# MBO.net
KiCad netlist of a schematic drawn in EAGLE
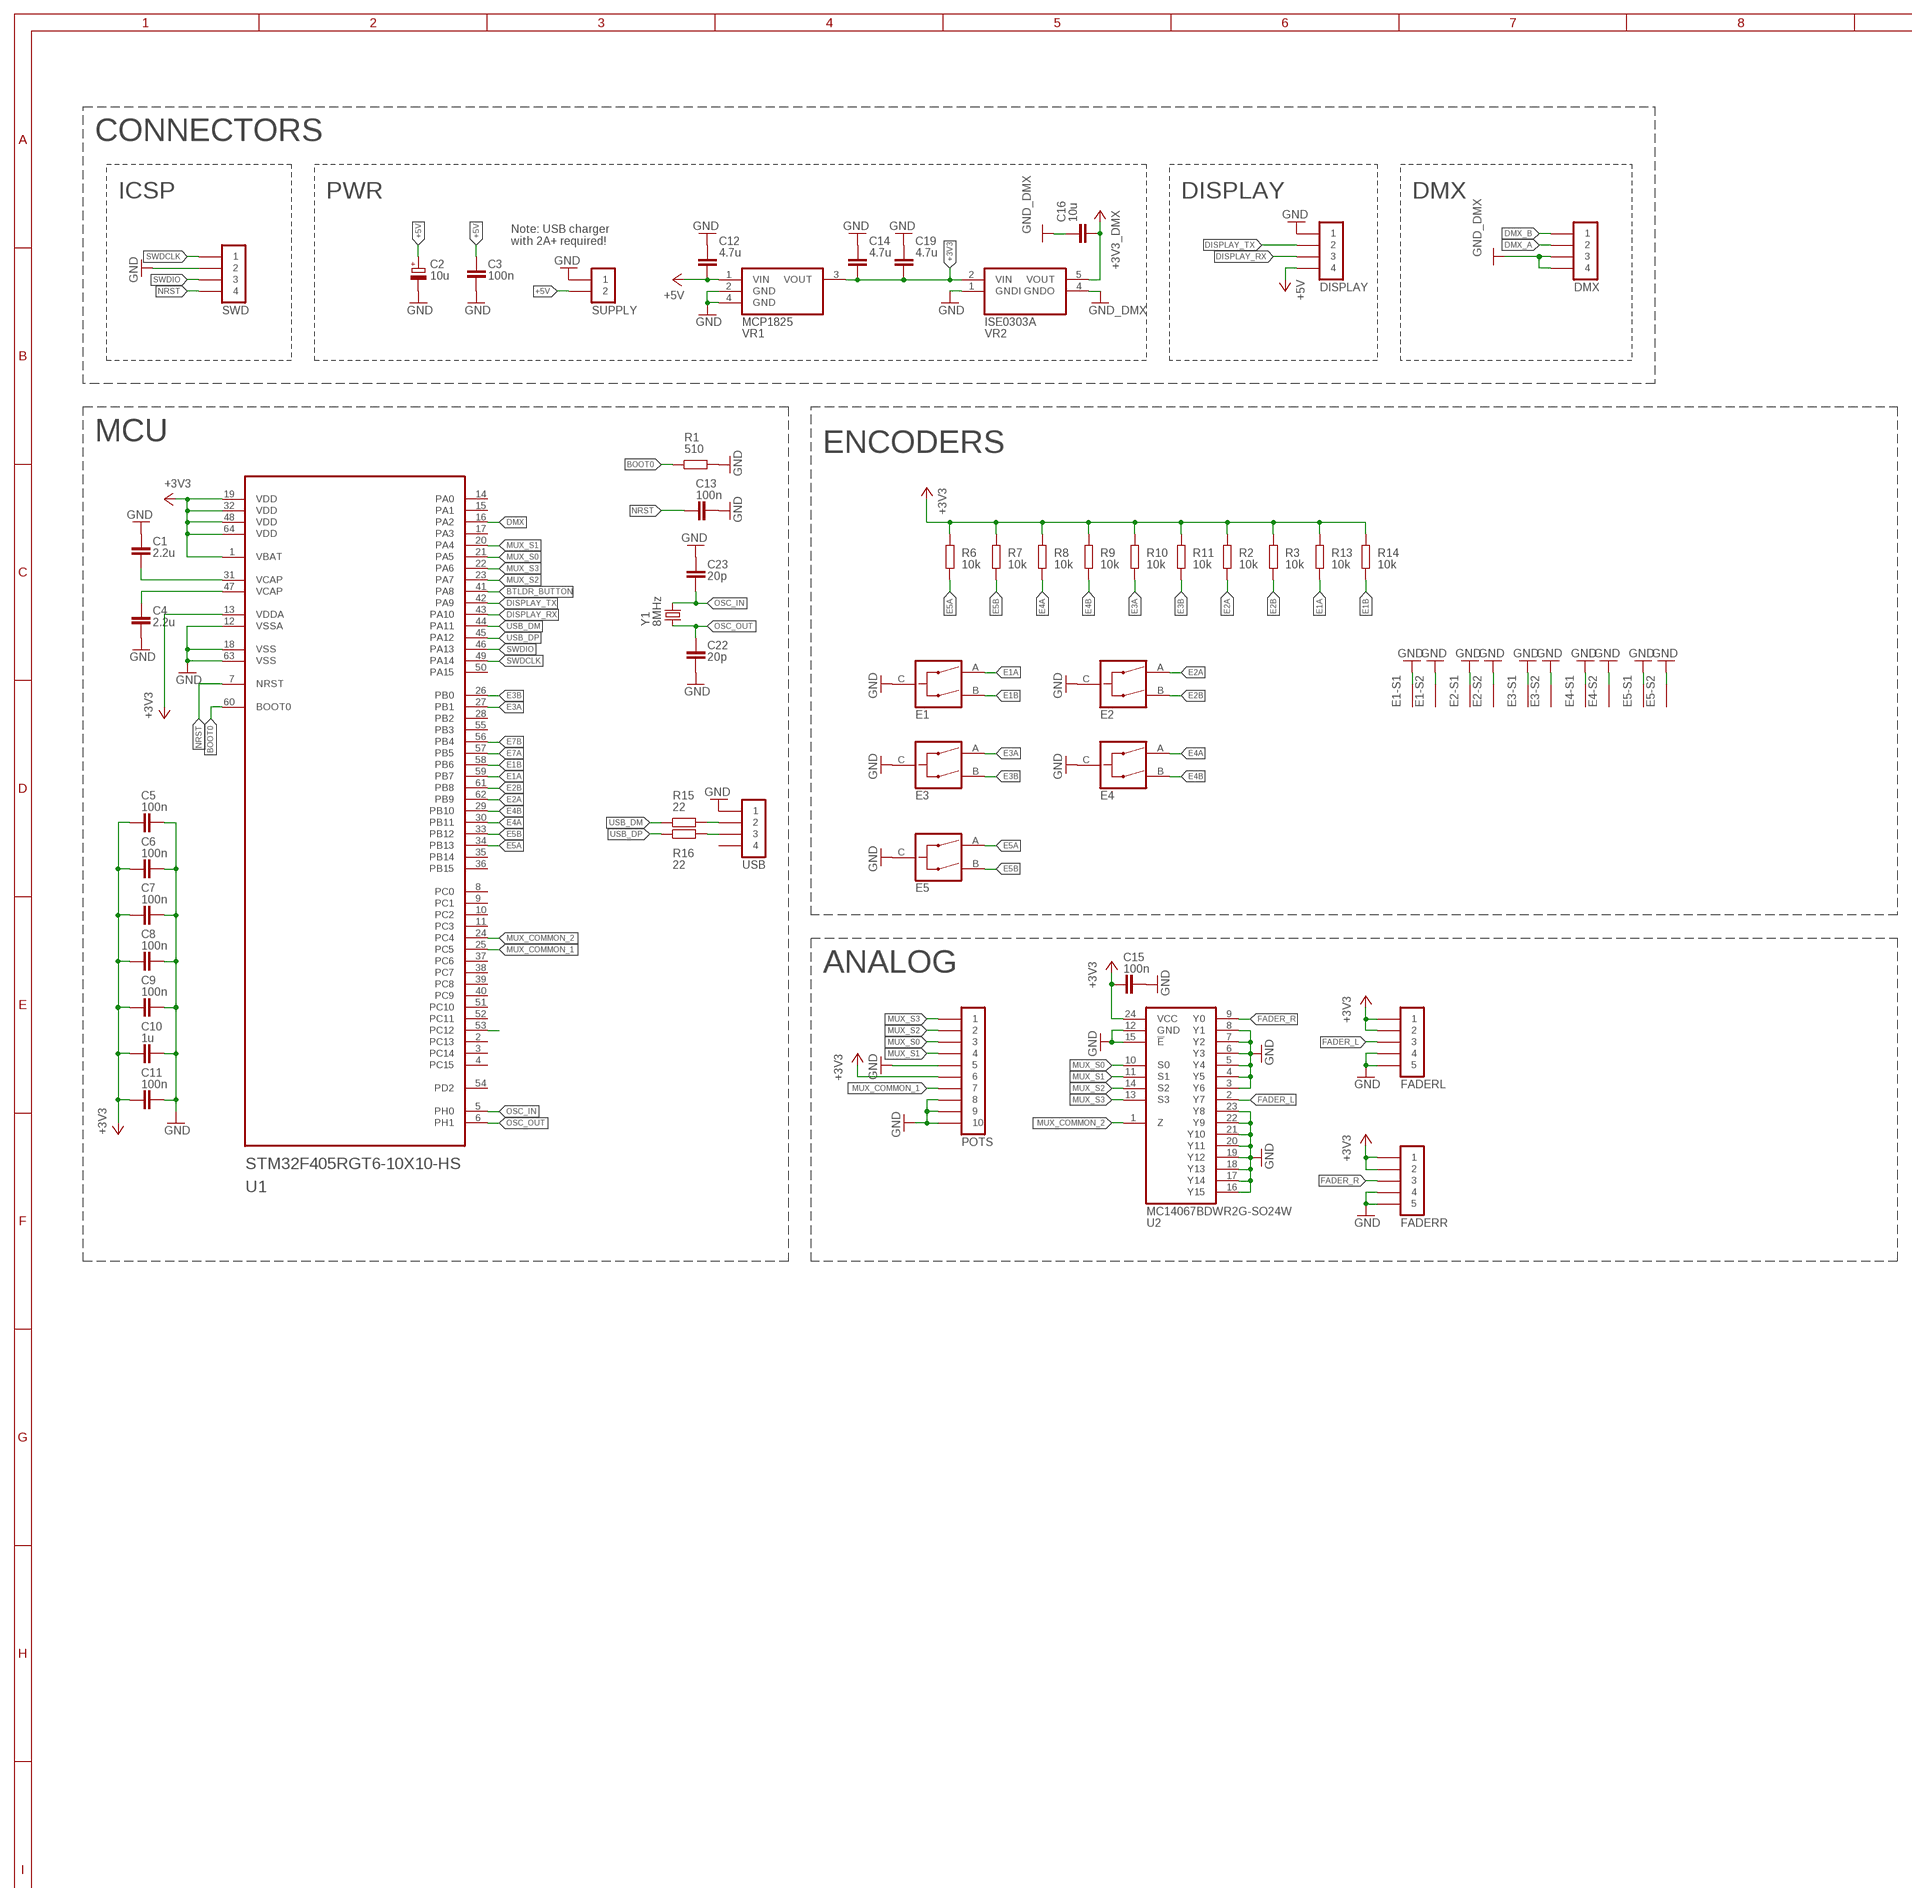
[diagram p0: schematic, sheet 1, part 1 of 2]
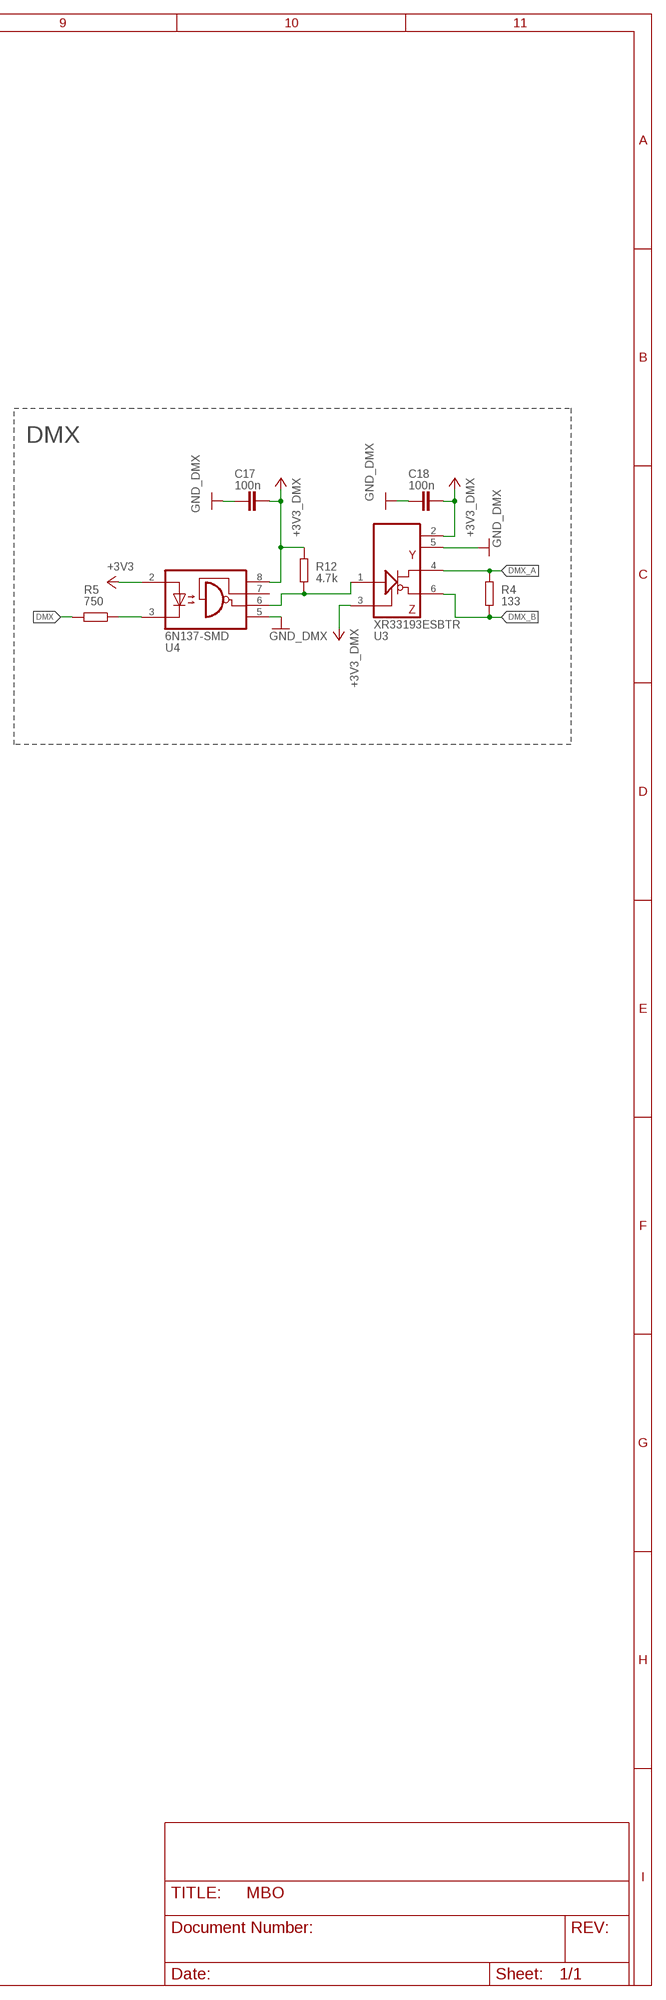
[diagram p1: schematic, sheet 1, part 2 of 2]

(export (version "E")
  (design (tool "Eeschema 10.0.6"))
  (components
    (comp (ref "C1")
      (value "2.2u")
      (footprint "eagle-import:C0805")
      (libsource (lib "eagle-import") (part "CAPACITOR-0805"))
    )
    (comp (ref "C2")
      (value "10u")
      (footprint "eagle-import:C-TH-E-0401")
      (libsource (lib "eagle-import") (part "ELECTROLYTIC_CAPACITOR-C-TH-E-0401"))
    )
    (comp (ref "C3")
      (value "100n")
      (footprint "eagle-import:C0805")
      (libsource (lib "eagle-import") (part "CAPACITOR-0805"))
    )
    (comp (ref "C4")
      (value "2.2u")
      (footprint "eagle-import:C0805")
      (libsource (lib "eagle-import") (part "CAPACITOR-0805"))
    )
    (comp (ref "C5")
      (value "100n")
      (footprint "eagle-import:C0805")
      (libsource (lib "eagle-import") (part "CAPACITOR-0805"))
    )
    (comp (ref "C6")
      (value "100n")
      (footprint "eagle-import:C0805")
      (libsource (lib "eagle-import") (part "CAPACITOR-0805"))
    )
    (comp (ref "C7")
      (value "100n")
      (footprint "eagle-import:C0805")
      (libsource (lib "eagle-import") (part "CAPACITOR-0805"))
    )
    (comp (ref "C8")
      (value "100n")
      (footprint "eagle-import:C0805")
      (libsource (lib "eagle-import") (part "CAPACITOR-0805"))
    )
    (comp (ref "C9")
      (value "100n")
      (footprint "eagle-import:C0805")
      (libsource (lib "eagle-import") (part "CAPACITOR-0805"))
    )
    (comp (ref "C10")
      (value "1u")
      (footprint "eagle-import:C0805")
      (libsource (lib "eagle-import") (part "CAPACITOR-0805"))
    )
    (comp (ref "C11")
      (value "100n")
      (footprint "eagle-import:C0805")
      (libsource (lib "eagle-import") (part "CAPACITOR-0805"))
    )
    (comp (ref "C12")
      (value "4.7u")
      (footprint "eagle-import:C0805")
      (libsource (lib "eagle-import") (part "CAPACITOR-0805"))
    )
    (comp (ref "C13")
      (value "100n")
      (footprint "eagle-import:C0805")
      (libsource (lib "eagle-import") (part "CAPACITOR-0805"))
    )
    (comp (ref "C14")
      (value "4.7u")
      (footprint "eagle-import:C0805")
      (libsource (lib "eagle-import") (part "CAPACITOR-0805"))
    )
    (comp (ref "C15")
      (value "100n")
      (footprint "eagle-import:C0805")
      (libsource (lib "eagle-import") (part "CAPACITOR-0805"))
    )
    (comp (ref "C16")
      (value "10u")
      (footprint "eagle-import:C0805")
      (libsource (lib "eagle-import") (part "CAPACITOR-0805"))
    )
    (comp (ref "C17")
      (value "100n")
      (footprint "eagle-import:C0805")
      (libsource (lib "eagle-import") (part "CAPACITOR-0805"))
    )
    (comp (ref "C18")
      (value "100n")
      (footprint "eagle-import:C0805")
      (libsource (lib "eagle-import") (part "CAPACITOR-0805"))
    )
    (comp (ref "C19")
      (value "4.7u")
      (footprint "eagle-import:C0805")
      (libsource (lib "eagle-import") (part "CAPACITOR-0805"))
    )
    (comp (ref "C22")
      (value "20p")
      (footprint "eagle-import:C0805")
      (libsource (lib "eagle-import") (part "CAPACITOR-0805"))
    )
    (comp (ref "C23")
      (value "20p")
      (footprint "eagle-import:C0805")
      (libsource (lib "eagle-import") (part "CAPACITOR-0805"))
    )
    (comp (ref "DISPLAY")
      (value "PINHD-1X04-JST-XH-H")
      (footprint "eagle-import:JST-XH-04P-H")
      (libsource (lib "eagle-import") (part "PINHD-1X04-JST-XH-H"))
    )
    (comp (ref "DMX")
      (value "PINHD-1X04-JST-XH-H")
      (footprint "eagle-import:JST-XH-04P-H")
      (libsource (lib "eagle-import") (part "PINHD-1X04-JST-XH-H"))
    )
    (comp (ref "E1")
      (value "ALPS-EC12E24404AX")
      (footprint "eagle-import:EC12E-1")
      (fields (field (name "MANUFACTURER") "ALPS") (field (name "MPN") "EC12E24404A8"))
      (libsource (lib "eagle-import") (part "ALPS-EC12E24404AX"))
    )
    (comp (ref "E2")
      (value "ALPS-EC12E24404AX")
      (footprint "eagle-import:EC12E-1")
      (fields (field (name "MANUFACTURER") "ALPS") (field (name "MPN") "EC12E24404A8"))
      (libsource (lib "eagle-import") (part "ALPS-EC12E24404AX"))
    )
    (comp (ref "E3")
      (value "ALPS-EC12E24404AX")
      (footprint "eagle-import:EC12E-1")
      (fields (field (name "MANUFACTURER") "ALPS") (field (name "MPN") "EC12E24404A8"))
      (libsource (lib "eagle-import") (part "ALPS-EC12E24404AX"))
    )
    (comp (ref "E4")
      (value "ALPS-EC12E24404AX")
      (footprint "eagle-import:EC12E-1")
      (fields (field (name "MANUFACTURER") "ALPS") (field (name "MPN") "EC12E24404A8"))
      (libsource (lib "eagle-import") (part "ALPS-EC12E24404AX"))
    )
    (comp (ref "E5")
      (value "ALPS-EC12E24404AX")
      (footprint "eagle-import:EC12E-1")
      (fields (field (name "MANUFACTURER") "ALPS") (field (name "MPN") "EC12E24404A8"))
      (libsource (lib "eagle-import") (part "ALPS-EC12E24404AX"))
    )
    (comp (ref "FADERL")
      (value "PINHD-1X05-FFC-1MM-Z")
      (footprint "eagle-import:MOLEX-52271-0579")
      (fields (field (name "MANUFACTURER") "Molex") (field (name "MPN") "52271-0579"))
      (libsource (lib "eagle-import") (part "PINHD-1X05-FFC-1MM-Z"))
    )
    (comp (ref "FADERR")
      (value "PINHD-1X05-FFC-1MM-Z")
      (footprint "eagle-import:MOLEX-52271-0579")
      (fields (field (name "MANUFACTURER") "Molex") (field (name "MPN") "52271-0579"))
      (libsource (lib "eagle-import") (part "PINHD-1X05-FFC-1MM-Z"))
    )
    (comp (ref "POTS")
      (value "PINHD-1X10-FFC-1MM-Z")
      (footprint "eagle-import:MOLEX-52271-1079")
      (fields (field (name "MANUFACTURER") "Molex") (field (name "MPN") "52271-1079"))
      (libsource (lib "eagle-import") (part "PINHD-1X10-FFC-1MM-Z"))
    )
    (comp (ref "R1")
      (value "510")
      (footprint "eagle-import:R0805")
      (libsource (lib "eagle-import") (part "RESISTOR-0805"))
    )
    (comp (ref "R2")
      (value "10k")
      (footprint "eagle-import:R0805")
      (libsource (lib "eagle-import") (part "RESISTOR-0805"))
    )
    (comp (ref "R3")
      (value "10k")
      (footprint "eagle-import:R0805")
      (libsource (lib "eagle-import") (part "RESISTOR-0805"))
    )
    (comp (ref "R4")
      (value "133")
      (footprint "eagle-import:R0805")
      (libsource (lib "eagle-import") (part "RESISTOR-0805"))
    )
    (comp (ref "R5")
      (value "750")
      (footprint "eagle-import:R0805")
      (libsource (lib "eagle-import") (part "RESISTOR-0805"))
    )
    (comp (ref "R6")
      (value "10k")
      (footprint "eagle-import:R0805")
      (libsource (lib "eagle-import") (part "RESISTOR-0805"))
    )
    (comp (ref "R7")
      (value "10k")
      (footprint "eagle-import:R0805")
      (libsource (lib "eagle-import") (part "RESISTOR-0805"))
    )
    (comp (ref "R8")
      (value "10k")
      (footprint "eagle-import:R0805")
      (libsource (lib "eagle-import") (part "RESISTOR-0805"))
    )
    (comp (ref "R9")
      (value "10k")
      (footprint "eagle-import:R0805")
      (libsource (lib "eagle-import") (part "RESISTOR-0805"))
    )
    (comp (ref "R10")
      (value "10k")
      (footprint "eagle-import:R0805")
      (libsource (lib "eagle-import") (part "RESISTOR-0805"))
    )
    (comp (ref "R11")
      (value "10k")
      (footprint "eagle-import:R0805")
      (libsource (lib "eagle-import") (part "RESISTOR-0805"))
    )
    (comp (ref "R12")
      (value "4.7k")
      (footprint "eagle-import:R0805")
      (libsource (lib "eagle-import") (part "RESISTOR-0805"))
    )
    (comp (ref "R13")
      (value "10k")
      (footprint "eagle-import:R0805")
      (libsource (lib "eagle-import") (part "RESISTOR-0805"))
    )
    (comp (ref "R14")
      (value "10k")
      (footprint "eagle-import:R0805")
      (libsource (lib "eagle-import") (part "RESISTOR-0805"))
    )
    (comp (ref "R15")
      (value "22")
      (footprint "eagle-import:R0805")
      (libsource (lib "eagle-import") (part "RESISTOR-0805"))
    )
    (comp (ref "R16")
      (value "22")
      (footprint "eagle-import:R0805")
      (libsource (lib "eagle-import") (part "RESISTOR-0805"))
    )
    (comp (ref "SUPPLY")
      (value "PINHD-1X02-JST-XH-H")
      (footprint "eagle-import:JST-XH-02P-H")
      (libsource (lib "eagle-import") (part "PINHD-1X02-JST-XH-H"))
    )
    (comp (ref "SWD")
      (value "PINHD-1X04-TH-2.54MM")
      (footprint "eagle-import:1X04-2.54")
      (libsource (lib "eagle-import") (part "PINHD-1X04-TH-2.54MM"))
    )
    (comp (ref "U1")
      (value "STM32F405RGT6-10X10-HS")
      (footprint "eagle-import:TQFP-64-10X10-HS")
      (fields (field (name "MANUFACTURER") "ST Microelectronics") (field (name "MPN") "STM32F405RGT6"))
      (libsource (lib "eagle-import") (part "STM32F405RGT6-10X10-HS"))
    )
    (comp (ref "U2")
      (value "MC14067BDWR2G-SO24W")
      (footprint "eagle-import:SO24-W")
      (fields (field (name "MANUFACTURER") "ON Semiconductor") (field (name "MPN") "MC14067BDWR2G"))
      (libsource (lib "eagle-import") (part "MC14067BDWR2G-SO24W"))
    )
    (comp (ref "U3")
      (value "XR33193ESBTR")
      (footprint "eagle-import:TSOT23-6")
      (fields (field (name "MANUFACTURER") "MaxLinear"))
      (libsource (lib "eagle-import") (part "XR33193ESBTR"))
    )
    (comp (ref "U4")
      (value "6N137-SMD")
      (footprint "eagle-import:SMD-8")
      (fields (field (name "MANUFACTURER") "Lite-On") (field (name "MPN") "6N137S"))
      (libsource (lib "eagle-import") (part "6N137-SMD"))
    )
    (comp (ref "USB")
      (value "PINHD-1X04-JST-XH-H")
      (footprint "eagle-import:JST-XH-04P-H")
      (libsource (lib "eagle-import") (part "PINHD-1X04-JST-XH-H"))
    )
    (comp (ref "VR1")
      (value "MCP1825")
      (footprint "eagle-import:SOT223")
      (fields (field (name "MANUFACTURER") "Microchip") (field (name "MPN") "MCP1825S-3302E/DB"))
      (libsource (lib "eagle-import") (part "MCP1825"))
    )
    (comp (ref "VR2")
      (value "ISE0303A")
      (footprint "eagle-import:SMD-8-5")
      (libsource (lib "eagle-import") (part "ISE0303A"))
    )
    (comp (ref "Y1")
      (value "8MHz")
      (footprint "eagle-import:HC49US")
      (fields (field (name "MANUFACTURER") "TXC") (field (name "MPN") "9B-16.000MEEJ-B"))
      (libsource (lib "eagle-import") (part "CRYSTAL-HC49"))
    )
  )
  (nets
    (net (code "1") (name "+3V3") (class "Default")
      (node (ref "C10") (pin "1") (pinfunction "1_1") (pintype "passive"))
      (node (ref "C11") (pin "1") (pinfunction "1_1") (pintype "passive"))
      (node (ref "C14") (pin "1") (pinfunction "1_1") (pintype "passive"))
      (node (ref "C15") (pin "1") (pinfunction "1_1") (pintype "passive"))
      (node (ref "C19") (pin "1") (pinfunction "1_1") (pintype "passive"))
      (node (ref "C5") (pin "1") (pinfunction "1_1") (pintype "passive"))
      (node (ref "C6") (pin "1") (pinfunction "1_1") (pintype "passive"))
      (node (ref "C7") (pin "1") (pinfunction "1_1") (pintype "passive"))
      (node (ref "C8") (pin "1") (pinfunction "1_1") (pintype "passive"))
      (node (ref "C9") (pin "1") (pinfunction "1_1") (pintype "passive"))
      (node (ref "FADERL") (pin "1") (pinfunction "1_1") (pintype "passive"))
      (node (ref "FADERL") (pin "2") (pinfunction "2_2") (pintype "passive"))
      (node (ref "FADERR") (pin "1") (pinfunction "1_1") (pintype "passive"))
      (node (ref "FADERR") (pin "2") (pinfunction "2_2") (pintype "passive"))
      (node (ref "POTS") (pin "6") (pinfunction "6_6") (pintype "passive"))
      (node (ref "R10") (pin "2") (pinfunction "2_2") (pintype "passive"))
      (node (ref "R11") (pin "2") (pinfunction "2_2") (pintype "passive"))
      (node (ref "R13") (pin "2") (pinfunction "2_2") (pintype "passive"))
      (node (ref "R14") (pin "2") (pinfunction "2_2") (pintype "passive"))
      (node (ref "R2") (pin "2") (pinfunction "2_2") (pintype "passive"))
      (node (ref "R3") (pin "2") (pinfunction "2_2") (pintype "passive"))
      (node (ref "R6") (pin "2") (pinfunction "2_2") (pintype "passive"))
      (node (ref "R7") (pin "2") (pinfunction "2_2") (pintype "passive"))
      (node (ref "R8") (pin "2") (pinfunction "2_2") (pintype "passive"))
      (node (ref "R9") (pin "2") (pinfunction "2_2") (pintype "passive"))
      (node (ref "U1") (pin "1") (pinfunction "VBAT_1") (pintype "bidirectional"))
      (node (ref "U1") (pin "13") (pinfunction "VDDA_13") (pintype "bidirectional"))
      (node (ref "U1") (pin "19") (pinfunction "VDD_19") (pintype "bidirectional"))
      (node (ref "U1") (pin "32") (pinfunction "VDD_32") (pintype "bidirectional"))
      (node (ref "U1") (pin "48") (pinfunction "VDD_48") (pintype "bidirectional"))
      (node (ref "U1") (pin "64") (pinfunction "VDD_64") (pintype "bidirectional"))
      (node (ref "U2") (pin "24") (pinfunction "VCC_24") (pintype "passive"))
      (node (ref "U4") (pin "2") (pinfunction "A_2") (pintype "passive"))
      (node (ref "VR1") (pin "3") (pinfunction "VOUT_3") (pintype "passive"))
      (node (ref "VR2") (pin "2") (pinfunction "VIN_2") (pintype "passive"))
    )
    (net (code "2") (name "+3V3_DMX") (class "Default")
      (node (ref "C16") (pin "1") (pinfunction "1_1") (pintype "passive"))
      (node (ref "C17") (pin "2") (pinfunction "2_2") (pintype "passive"))
      (node (ref "C18") (pin "2") (pinfunction "2_2") (pintype "passive"))
      (node (ref "R12") (pin "2") (pinfunction "2_2") (pintype "passive"))
      (node (ref "U3") (pin "2") (pinfunction "VCC_2") (pintype "passive"))
      (node (ref "U3") (pin "3") (pinfunction "DE_3") (pintype "bidirectional"))
      (node (ref "U4") (pin "8") (pinfunction "VCC_8") (pintype "power_in"))
      (node (ref "VR2") (pin "5") (pinfunction "VOUT_5") (pintype "passive"))
    )
    (net (code "3") (name "+5V") (class "Default")
      (node (ref "C12") (pin "1") (pinfunction "1_1") (pintype "passive"))
      (node (ref "C2") (pin "+") (pinfunction "+_+") (pintype "passive"))
      (node (ref "C3") (pin "1") (pinfunction "1_1") (pintype "passive"))
      (node (ref "DISPLAY") (pin "4") (pinfunction "4_4") (pintype "passive"))
      (node (ref "SUPPLY") (pin "2") (pinfunction "2_2") (pintype "passive"))
      (node (ref "VR1") (pin "1") (pinfunction "VIN_1") (pintype "passive"))
    )
    (net (code "4") (name "BOOT0") (class "Default")
      (node (ref "R1") (pin "1") (pinfunction "1_1") (pintype "passive"))
      (node (ref "U1") (pin "60") (pinfunction "BOOT0_60") (pintype "bidirectional"))
    )
    (net (code "5") (name "BTLDR_BUTTON") (class "Default")
      (node (ref "U1") (pin "41") (pinfunction "PA8_41") (pintype "bidirectional"))
    )
    (net (code "6") (name "DISPLAY_RX") (class "Default")
      (node (ref "DISPLAY") (pin "3") (pinfunction "3_3") (pintype "passive"))
      (node (ref "U1") (pin "43") (pinfunction "PA10_43") (pintype "bidirectional"))
    )
    (net (code "7") (name "DISPLAY_TX") (class "Default")
      (node (ref "DISPLAY") (pin "2") (pinfunction "2_2") (pintype "passive"))
      (node (ref "U1") (pin "42") (pinfunction "PA9_42") (pintype "bidirectional"))
    )
    (net (code "8") (name "DMX") (class "Default")
      (node (ref "R5") (pin "2") (pinfunction "2_2") (pintype "passive"))
      (node (ref "U1") (pin "16") (pinfunction "PA2_16") (pintype "bidirectional"))
    )
    (net (code "9") (name "DMX_A") (class "Default")
      (node (ref "DMX") (pin "2") (pinfunction "2_2") (pintype "passive"))
      (node (ref "R4") (pin "2") (pinfunction "2_2") (pintype "passive"))
      (node (ref "U3") (pin "4") (pinfunction "B_4") (pintype "output"))
    )
    (net (code "10") (name "DMX_B") (class "Default")
      (node (ref "DMX") (pin "1") (pinfunction "1_1") (pintype "passive"))
      (node (ref "R4") (pin "1") (pinfunction "1_1") (pintype "passive"))
      (node (ref "U3") (pin "6") (pinfunction "A_6") (pintype "output"))
    )
    (net (code "11") (name "E1A") (class "Default")
      (node (ref "E1") (pin "A") (pinfunction "A_A") (pintype "output"))
      (node (ref "R13") (pin "1") (pinfunction "1_1") (pintype "passive"))
      (node (ref "U1") (pin "59") (pinfunction "PB7_59") (pintype "bidirectional"))
    )
    (net (code "12") (name "E1B") (class "Default")
      (node (ref "E1") (pin "B") (pinfunction "B_B") (pintype "output"))
      (node (ref "R14") (pin "1") (pinfunction "1_1") (pintype "passive"))
      (node (ref "U1") (pin "58") (pinfunction "PB6_58") (pintype "bidirectional"))
    )
    (net (code "13") (name "E2A") (class "Default")
      (node (ref "E2") (pin "A") (pinfunction "A_A") (pintype "output"))
      (node (ref "R2") (pin "1") (pinfunction "1_1") (pintype "passive"))
      (node (ref "U1") (pin "62") (pinfunction "PB9_62") (pintype "bidirectional"))
    )
    (net (code "14") (name "E2B") (class "Default")
      (node (ref "E2") (pin "B") (pinfunction "B_B") (pintype "output"))
      (node (ref "R3") (pin "1") (pinfunction "1_1") (pintype "passive"))
      (node (ref "U1") (pin "61") (pinfunction "PB8_61") (pintype "bidirectional"))
    )
    (net (code "15") (name "E3A") (class "Default")
      (node (ref "E3") (pin "A") (pinfunction "A_A") (pintype "output"))
      (node (ref "R10") (pin "1") (pinfunction "1_1") (pintype "passive"))
      (node (ref "U1") (pin "27") (pinfunction "PB1_27") (pintype "bidirectional"))
    )
    (net (code "16") (name "E3B") (class "Default")
      (node (ref "E3") (pin "B") (pinfunction "B_B") (pintype "output"))
      (node (ref "R11") (pin "1") (pinfunction "1_1") (pintype "passive"))
      (node (ref "U1") (pin "26") (pinfunction "PB0_26") (pintype "bidirectional"))
    )
    (net (code "17") (name "E4A") (class "Default")
      (node (ref "E4") (pin "A") (pinfunction "A_A") (pintype "output"))
      (node (ref "R8") (pin "1") (pinfunction "1_1") (pintype "passive"))
      (node (ref "U1") (pin "30") (pinfunction "PB11_30") (pintype "bidirectional"))
    )
    (net (code "18") (name "E4B") (class "Default")
      (node (ref "E4") (pin "B") (pinfunction "B_B") (pintype "output"))
      (node (ref "R9") (pin "1") (pinfunction "1_1") (pintype "passive"))
      (node (ref "U1") (pin "29") (pinfunction "PB10_29") (pintype "bidirectional"))
    )
    (net (code "19") (name "E5A") (class "Default")
      (node (ref "E5") (pin "A") (pinfunction "A_A") (pintype "output"))
      (node (ref "R6") (pin "1") (pinfunction "1_1") (pintype "passive"))
      (node (ref "U1") (pin "34") (pinfunction "PB13_34") (pintype "bidirectional"))
    )
    (net (code "20") (name "E5B") (class "Default")
      (node (ref "E5") (pin "B") (pinfunction "B_B") (pintype "output"))
      (node (ref "R7") (pin "1") (pinfunction "1_1") (pintype "passive"))
      (node (ref "U1") (pin "33") (pinfunction "PB12_33") (pintype "bidirectional"))
    )
    (net (code "21") (name "E7A") (class "Default")
      (node (ref "U1") (pin "57") (pinfunction "PB5_57") (pintype "bidirectional"))
    )
    (net (code "22") (name "E7B") (class "Default")
      (node (ref "U1") (pin "56") (pinfunction "PB4_56") (pintype "bidirectional"))
    )
    (net (code "23") (name "FADER_L") (class "Default")
      (node (ref "FADERL") (pin "3") (pinfunction "3_3") (pintype "passive"))
      (node (ref "U2") (pin "2") (pinfunction "Y7_2") (pintype "bidirectional"))
    )
    (net (code "24") (name "FADER_R") (class "Default")
      (node (ref "FADERR") (pin "3") (pinfunction "3_3") (pintype "passive"))
      (node (ref "U2") (pin "9") (pinfunction "Y0_9") (pintype "bidirectional"))
    )
    (net (code "25") (name "GND") (class "Default")
      (node (ref "C1") (pin "1") (pinfunction "1_1") (pintype "passive"))
      (node (ref "C10") (pin "2") (pinfunction "2_2") (pintype "passive"))
      (node (ref "C11") (pin "2") (pinfunction "2_2") (pintype "passive"))
      (node (ref "C12") (pin "2") (pinfunction "2_2") (pintype "passive"))
      (node (ref "C13") (pin "2") (pinfunction "2_2") (pintype "passive"))
      (node (ref "C14") (pin "2") (pinfunction "2_2") (pintype "passive"))
      (node (ref "C15") (pin "2") (pinfunction "2_2") (pintype "passive"))
      (node (ref "C19") (pin "2") (pinfunction "2_2") (pintype "passive"))
      (node (ref "C2") (pin "-") (pinfunction "-_-") (pintype "passive"))
      (node (ref "C22") (pin "2") (pinfunction "2_2") (pintype "passive"))
      (node (ref "C23") (pin "1") (pinfunction "1_1") (pintype "passive"))
      (node (ref "C3") (pin "2") (pinfunction "2_2") (pintype "passive"))
      (node (ref "C4") (pin "2") (pinfunction "2_2") (pintype "passive"))
      (node (ref "C5") (pin "2") (pinfunction "2_2") (pintype "passive"))
      (node (ref "C6") (pin "2") (pinfunction "2_2") (pintype "passive"))
      (node (ref "C7") (pin "2") (pinfunction "2_2") (pintype "passive"))
      (node (ref "C8") (pin "2") (pinfunction "2_2") (pintype "passive"))
      (node (ref "C9") (pin "2") (pinfunction "2_2") (pintype "passive"))
      (node (ref "DISPLAY") (pin "1") (pinfunction "1_1") (pintype "passive"))
      (node (ref "E1") (pin "C") (pinfunction "C_C") (pintype "input"))
      (node (ref "E1") (pin "S1") (pinfunction "S_S1") (pintype "passive"))
      (node (ref "E1") (pin "S2") (pinfunction "S_S2") (pintype "passive"))
      (node (ref "E2") (pin "C") (pinfunction "C_C") (pintype "input"))
      (node (ref "E2") (pin "S1") (pinfunction "S_S1") (pintype "passive"))
      (node (ref "E2") (pin "S2") (pinfunction "S_S2") (pintype "passive"))
      (node (ref "E3") (pin "C") (pinfunction "C_C") (pintype "input"))
      (node (ref "E3") (pin "S1") (pinfunction "S_S1") (pintype "passive"))
      (node (ref "E3") (pin "S2") (pinfunction "S_S2") (pintype "passive"))
      (node (ref "E4") (pin "C") (pinfunction "C_C") (pintype "input"))
      (node (ref "E4") (pin "S1") (pinfunction "S_S1") (pintype "passive"))
      (node (ref "E4") (pin "S2") (pinfunction "S_S2") (pintype "passive"))
      (node (ref "E5") (pin "C") (pinfunction "C_C") (pintype "input"))
      (node (ref "E5") (pin "S1") (pinfunction "S_S1") (pintype "passive"))
      (node (ref "E5") (pin "S2") (pinfunction "S_S2") (pintype "passive"))
      (node (ref "FADERL") (pin "4") (pinfunction "4_4") (pintype "passive"))
      (node (ref "FADERL") (pin "5") (pinfunction "5_5") (pintype "passive"))
      (node (ref "FADERR") (pin "4") (pinfunction "4_4") (pintype "passive"))
      (node (ref "FADERR") (pin "5") (pinfunction "5_5") (pintype "passive"))
      (node (ref "POTS") (pin "10") (pinfunction "10_10") (pintype "passive"))
      (node (ref "POTS") (pin "5") (pinfunction "5_5") (pintype "passive"))
      (node (ref "POTS") (pin "8") (pinfunction "8_8") (pintype "passive"))
      (node (ref "POTS") (pin "9") (pinfunction "9_9") (pintype "passive"))
      (node (ref "R1") (pin "2") (pinfunction "2_2") (pintype "passive"))
      (node (ref "SUPPLY") (pin "1") (pinfunction "1_1") (pintype "passive"))
      (node (ref "SWD") (pin "2") (pinfunction "2_2") (pintype "passive"))
      (node (ref "U1") (pin "12") (pinfunction "VSSA_12") (pintype "bidirectional"))
      (node (ref "U1") (pin "18") (pinfunction "VSS_18") (pintype "bidirectional"))
      (node (ref "U1") (pin "63") (pinfunction "VSS_63") (pintype "bidirectional"))
      (node (ref "U2") (pin "12") (pinfunction "GND_12") (pintype "passive"))
      (node (ref "U2") (pin "15") (pinfunction "~{E}_15") (pintype "input"))
      (node (ref "U2") (pin "16") (pinfunction "Y15_16") (pintype "bidirectional"))
      (node (ref "U2") (pin "17") (pinfunction "Y14_17") (pintype "bidirectional"))
      (node (ref "U2") (pin "18") (pinfunction "Y13_18") (pintype "bidirectional"))
      (node (ref "U2") (pin "19") (pinfunction "Y12_19") (pintype "bidirectional"))
      (node (ref "U2") (pin "20") (pinfunction "Y11_20") (pintype "bidirectional"))
      (node (ref "U2") (pin "21") (pinfunction "Y10_21") (pintype "bidirectional"))
      (node (ref "U2") (pin "22") (pinfunction "Y9_22") (pintype "bidirectional"))
      (node (ref "U2") (pin "23") (pinfunction "Y8_23") (pintype "bidirectional"))
      (node (ref "U2") (pin "3") (pinfunction "Y6_3") (pintype "bidirectional"))
      (node (ref "U2") (pin "4") (pinfunction "Y5_4") (pintype "bidirectional"))
      (node (ref "U2") (pin "5") (pinfunction "Y4_5") (pintype "bidirectional"))
      (node (ref "U2") (pin "6") (pinfunction "Y3_6") (pintype "bidirectional"))
      (node (ref "U2") (pin "7") (pinfunction "Y2_7") (pintype "bidirectional"))
      (node (ref "U2") (pin "8") (pinfunction "Y1_8") (pintype "bidirectional"))
      (node (ref "USB") (pin "1") (pinfunction "1_1") (pintype "passive"))
      (node (ref "VR1") (pin "2") (pinfunction "GND_2") (pintype "passive"))
      (node (ref "VR1") (pin "4") (pinfunction "GND_4") (pintype "passive"))
      (node (ref "VR2") (pin "1") (pinfunction "GNDI_1") (pintype "passive"))
    )
    (net (code "26") (name "GND_DMX") (class "Default")
      (node (ref "C16") (pin "2") (pinfunction "2_2") (pintype "passive"))
      (node (ref "C17") (pin "1") (pinfunction "1_1") (pintype "passive"))
      (node (ref "C18") (pin "1") (pinfunction "1_1") (pintype "passive"))
      (node (ref "DMX") (pin "3") (pinfunction "3_3") (pintype "passive"))
      (node (ref "DMX") (pin "4") (pinfunction "4_4") (pintype "passive"))
      (node (ref "U3") (pin "5") (pinfunction "GND_5") (pintype "passive"))
      (node (ref "U4") (pin "5") (pinfunction "GND_5") (pintype "power_in"))
      (node (ref "VR2") (pin "4") (pinfunction "GNDO_4") (pintype "passive"))
    )
    (net (code "27") (name "MUX_COMMON_1") (class "Default")
      (node (ref "POTS") (pin "7") (pinfunction "7_7") (pintype "passive"))
      (node (ref "U1") (pin "25") (pinfunction "PC5_25") (pintype "bidirectional"))
    )
    (net (code "28") (name "MUX_COMMON_2") (class "Default")
      (node (ref "U1") (pin "24") (pinfunction "PC4_24") (pintype "bidirectional"))
      (node (ref "U2") (pin "1") (pinfunction "Z_1") (pintype "bidirectional"))
    )
    (net (code "29") (name "MUX_S0") (class "Default")
      (node (ref "POTS") (pin "3") (pinfunction "3_3") (pintype "passive"))
      (node (ref "U1") (pin "21") (pinfunction "PA5_21") (pintype "bidirectional"))
      (node (ref "U2") (pin "10") (pinfunction "S0_10") (pintype "input"))
    )
    (net (code "30") (name "MUX_S1") (class "Default")
      (node (ref "POTS") (pin "4") (pinfunction "4_4") (pintype "passive"))
      (node (ref "U1") (pin "20") (pinfunction "PA4_20") (pintype "bidirectional"))
      (node (ref "U2") (pin "11") (pinfunction "S1_11") (pintype "input"))
    )
    (net (code "31") (name "MUX_S2") (class "Default")
      (node (ref "POTS") (pin "2") (pinfunction "2_2") (pintype "passive"))
      (node (ref "U1") (pin "23") (pinfunction "PA7_23") (pintype "bidirectional"))
      (node (ref "U2") (pin "14") (pinfunction "S2_14") (pintype "input"))
    )
    (net (code "32") (name "MUX_S3") (class "Default")
      (node (ref "POTS") (pin "1") (pinfunction "1_1") (pintype "passive"))
      (node (ref "U1") (pin "22") (pinfunction "PA6_22") (pintype "bidirectional"))
      (node (ref "U2") (pin "13") (pinfunction "S3_13") (pintype "input"))
    )
    (net (code "33") (name "NRST") (class "Default")
      (node (ref "C13") (pin "1") (pinfunction "1_1") (pintype "passive"))
      (node (ref "SWD") (pin "4") (pinfunction "4_4") (pintype "passive"))
      (node (ref "U1") (pin "7") (pinfunction "NRST_7") (pintype "bidirectional"))
    )
    (net (code "34") (name "Net-(C1-Pad2)") (class "Default")
      (node (ref "C1") (pin "2") (pinfunction "2_2") (pintype "passive"))
      (node (ref "U1") (pin "31") (pinfunction "VCAP_31") (pintype "bidirectional"))
    )
    (net (code "35") (name "Net-(C4-Pad1)") (class "Default")
      (node (ref "C4") (pin "1") (pinfunction "1_1") (pintype "passive"))
      (node (ref "U1") (pin "47") (pinfunction "VCAP_47") (pintype "bidirectional"))
    )
    (net (code "36") (name "Net-(R15-Pad2)") (class "Default")
      (node (ref "R15") (pin "2") (pinfunction "2_2") (pintype "passive"))
      (node (ref "USB") (pin "2") (pinfunction "2_2") (pintype "passive"))
    )
    (net (code "37") (name "Net-(R16-Pad2)") (class "Default")
      (node (ref "R16") (pin "2") (pinfunction "2_2") (pintype "passive"))
      (node (ref "USB") (pin "3") (pinfunction "3_3") (pintype "passive"))
    )
    (net (code "38") (name "Net-(U3-DI)") (class "Default")
      (node (ref "R12") (pin "1") (pinfunction "1_1") (pintype "passive"))
      (node (ref "U3") (pin "1") (pinfunction "DI_1") (pintype "bidirectional"))
      (node (ref "U4") (pin "6") (pinfunction "VO_6") (pintype "output"))
    )
    (net (code "39") (name "Net-(U4-C)") (class "Default")
      (node (ref "R5") (pin "1") (pinfunction "1_1") (pintype "passive"))
      (node (ref "U4") (pin "3") (pinfunction "C_3") (pintype "passive"))
    )
    (net (code "40") (name "OSC_IN") (class "Default")
      (node (ref "C23") (pin "2") (pinfunction "2_2") (pintype "passive"))
      (node (ref "U1") (pin "5") (pinfunction "PH0_5") (pintype "bidirectional"))
      (node (ref "Y1") (pin "2") (pinfunction "2_2") (pintype "passive"))
    )
    (net (code "41") (name "OSC_OUT") (class "Default")
      (node (ref "C22") (pin "1") (pinfunction "1_1") (pintype "passive"))
      (node (ref "U1") (pin "6") (pinfunction "PH1_6") (pintype "bidirectional"))
      (node (ref "Y1") (pin "1") (pinfunction "1_1") (pintype "passive"))
    )
    (net (code "42") (name "SWDCLK") (class "Default")
      (node (ref "SWD") (pin "1") (pinfunction "1_1") (pintype "passive"))
      (node (ref "U1") (pin "49") (pinfunction "PA14_49") (pintype "bidirectional"))
    )
    (net (code "43") (name "SWDIO") (class "Default")
      (node (ref "SWD") (pin "3") (pinfunction "3_3") (pintype "passive"))
      (node (ref "U1") (pin "46") (pinfunction "PA13_46") (pintype "bidirectional"))
    )
    (net (code "44") (name "USB_DM") (class "Default")
      (node (ref "R15") (pin "1") (pinfunction "1_1") (pintype "passive"))
      (node (ref "U1") (pin "44") (pinfunction "PA11_44") (pintype "bidirectional"))
    )
    (net (code "45") (name "USB_DP") (class "Default")
      (node (ref "R16") (pin "1") (pinfunction "1_1") (pintype "passive"))
      (node (ref "U1") (pin "45") (pinfunction "PA12_45") (pintype "bidirectional"))
    )
    (net (code "46") (name "unconnected-(U1-PA0-Pad14)") (class "Default")
      (node (ref "U1") (pin "14") (pinfunction "PA0_14") (pintype "bidirectional"))
    )
    (net (code "47") (name "unconnected-(U1-PA1-Pad15)") (class "Default")
      (node (ref "U1") (pin "15") (pinfunction "PA1_15") (pintype "bidirectional"))
    )
    (net (code "48") (name "unconnected-(U1-PA3-Pad17)") (class "Default")
      (node (ref "U1") (pin "17") (pinfunction "PA3_17") (pintype "bidirectional"))
    )
    (net (code "49") (name "unconnected-(U1-PA15-Pad50)") (class "Default")
      (node (ref "U1") (pin "50") (pinfunction "PA15_50") (pintype "bidirectional"))
    )
    (net (code "50") (name "unconnected-(U1-PB2-Pad28)") (class "Default")
      (node (ref "U1") (pin "28") (pinfunction "PB2_28") (pintype "bidirectional"))
    )
    (net (code "51") (name "unconnected-(U1-PB3-Pad55)") (class "Default")
      (node (ref "U1") (pin "55") (pinfunction "PB3_55") (pintype "bidirectional"))
    )
    (net (code "52") (name "unconnected-(U1-PB14-Pad35)") (class "Default")
      (node (ref "U1") (pin "35") (pinfunction "PB14_35") (pintype "bidirectional"))
    )
    (net (code "53") (name "unconnected-(U1-PB15-Pad36)") (class "Default")
      (node (ref "U1") (pin "36") (pinfunction "PB15_36") (pintype "bidirectional"))
    )
    (net (code "54") (name "unconnected-(U1-PC0-Pad8)") (class "Default")
      (node (ref "U1") (pin "8") (pinfunction "PC0_8") (pintype "bidirectional"))
    )
    (net (code "55") (name "unconnected-(U1-PC1-Pad9)") (class "Default")
      (node (ref "U1") (pin "9") (pinfunction "PC1_9") (pintype "bidirectional"))
    )
    (net (code "56") (name "unconnected-(U1-PC2-Pad10)") (class "Default")
      (node (ref "U1") (pin "10") (pinfunction "PC2_10") (pintype "bidirectional"))
    )
    (net (code "57") (name "unconnected-(U1-PC3-Pad11)") (class "Default")
      (node (ref "U1") (pin "11") (pinfunction "PC3_11") (pintype "bidirectional"))
    )
    (net (code "58") (name "unconnected-(U1-PC6-Pad37)") (class "Default")
      (node (ref "U1") (pin "37") (pinfunction "PC6_37") (pintype "bidirectional"))
    )
    (net (code "59") (name "unconnected-(U1-PC7-Pad38)") (class "Default")
      (node (ref "U1") (pin "38") (pinfunction "PC7_38") (pintype "bidirectional"))
    )
    (net (code "60") (name "unconnected-(U1-PC8-Pad39)") (class "Default")
      (node (ref "U1") (pin "39") (pinfunction "PC8_39") (pintype "bidirectional"))
    )
    (net (code "61") (name "unconnected-(U1-PC9-Pad40)") (class "Default")
      (node (ref "U1") (pin "40") (pinfunction "PC9_40") (pintype "bidirectional"))
    )
    (net (code "62") (name "unconnected-(U1-PC10-Pad51)") (class "Default")
      (node (ref "U1") (pin "51") (pinfunction "PC10_51") (pintype "bidirectional"))
    )
    (net (code "63") (name "unconnected-(U1-PC11-Pad52)") (class "Default")
      (node (ref "U1") (pin "52") (pinfunction "PC11_52") (pintype "bidirectional"))
    )
    (net (code "64") (name "unconnected-(U1-PC12-Pad53)") (class "Default")
      (node (ref "U1") (pin "53") (pinfunction "PC12_53") (pintype "bidirectional"))
    )
    (net (code "65") (name "unconnected-(U1-PC13-Pad2)") (class "Default")
      (node (ref "U1") (pin "2") (pinfunction "PC13_2") (pintype "bidirectional"))
    )
    (net (code "66") (name "unconnected-(U1-PC14-Pad3)") (class "Default")
      (node (ref "U1") (pin "3") (pinfunction "PC14_3") (pintype "bidirectional"))
    )
    (net (code "67") (name "unconnected-(U1-PC15-Pad4)") (class "Default")
      (node (ref "U1") (pin "4") (pinfunction "PC15_4") (pintype "bidirectional"))
    )
    (net (code "68") (name "unconnected-(U1-PD2-Pad54)") (class "Default")
      (node (ref "U1") (pin "54") (pinfunction "PD2_54") (pintype "bidirectional"))
    )
    (net (code "69") (name "unconnected-(U4-VE-Pad7)") (class "Default")
      (node (ref "U4") (pin "7") (pinfunction "VE_7") (pintype "input"))
    )
    (net (code "70") (name "unconnected-(USB-Pad4)") (class "Default")
      (node (ref "USB") (pin "4") (pinfunction "4_4") (pintype "passive"))
    )
  )
)
